# STM32_MPU_IOs.net
KiCad netlist of a schematic drawn in Altium Designer
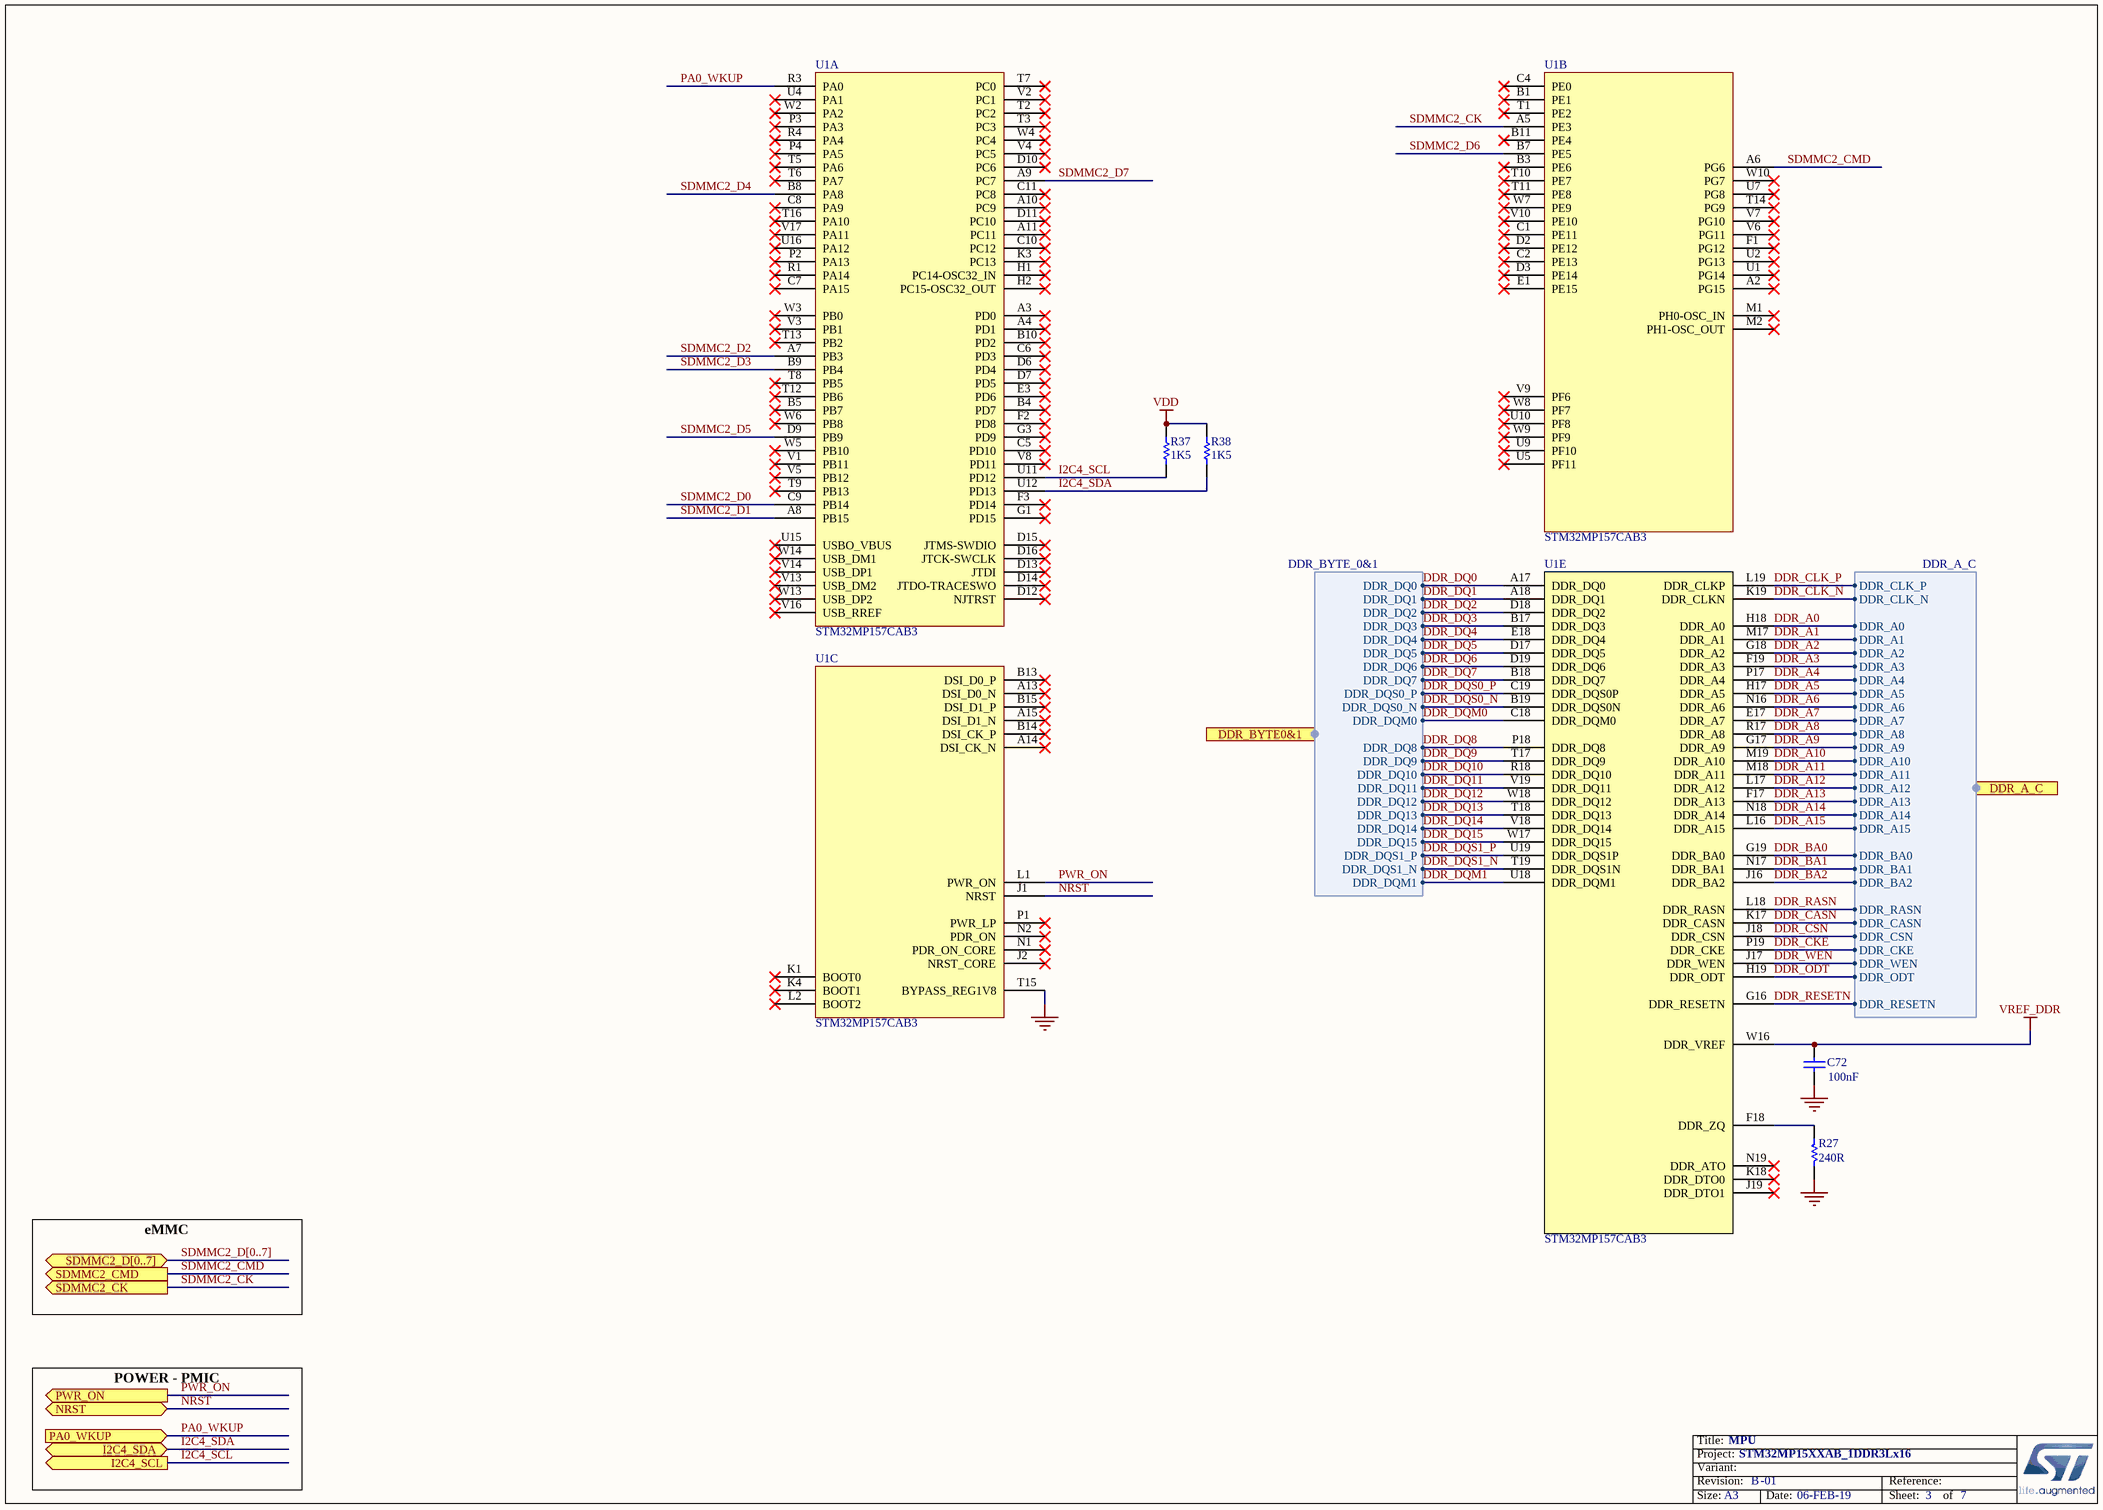
[diagram p0: STM32_MPU_IOs.SchDoc]

(export (version "E")
  (design (tool "Eeschema 10.0.6"))
  (components
    (comp (ref "C72")
      (value "100nF")
      (footprint "C0402")
      (description "Capacitor, MLCC, 100nF, 16V, X7R, 10%, 0402, T=0.5mm")
      (fields
        (field (name "INTERNAL_PART_NUMBER") "MCD-00006")
        (field (name "MANUFACTURER_PART_NUMBER") "CC0402KRX7R7BB104")
        (field (name "PROVIDED_BY") "SUBCO")
      )
      (libsource (lib "MCD_PARTS_database") (part "Capacitor"))
    )
    (comp (ref "R27")
      (value "240R")
      (footprint "R0402")
      (description "Resistor,240R,0402,1%,1/16W")
      (fields
        (field (name "INTERNAL_PART_NUMBER") "MCD-00120")
        (field (name "MANUFACTURER_PART_NUMBER") "RC0402FR-07240RL")
        (field (name "PROVIDED_BY") "SUBCO")
      )
      (libsource (lib "MCD_PARTS_database") (part "Resistor"))
    )
    (comp (ref "R37")
      (value "1K5")
      (footprint "R0402")
      (description "Resistor,1K5,0402,1%,1/16W")
      (fields
        (field (name "INTERNAL_PART_NUMBER") "MCD-00068")
        (field (name "MANUFACTURER_PART_NUMBER") "RC0402FR-071K5L")
        (field (name "PROVIDED_BY") "SUBCO")
      )
      (libsource (lib "MCD_PARTS_database") (part "Resistor"))
    )
    (comp (ref "R38")
      (value "1K5")
      (footprint "R0402")
      (description "Resistor,1K5,0402,1%,1/16W")
      (fields
        (field (name "INTERNAL_PART_NUMBER") "MCD-00068")
        (field (name "MANUFACTURER_PART_NUMBER") "RC0402FR-071K5L")
        (field (name "PROVIDED_BY") "SUBCO")
      )
      (libsource (lib "MCD_PARTS_database") (part "Resistor"))
    )
    (comp (ref "U1")
      (value "STM32MP157CAB3")
      (footprint "ICC_LFBGA354_16X16_STM32MP157CAB3_P080")
      (description "MPU LFBGA 16x16x1.271 PITCH 0.8 mm secure boot + crypto")
      (fields
        (field (name "INTERNAL_PART_NUMBER") "MCD-01805")
        (field (name "MANUFACTURER") "STMICROELECTRONICS")
        (field (name "PROVIDED_BY") "SUBCO with ST control")
      )
      (libsource (lib "MCD_PARTS_database") (part "STM32MP157CAB3"))
    )
  )
  (nets
    (net (code "3") (name "/DDR_A0") (class "Default")
      (node (ref "U1") (pin "H18") (pinfunction "DDR_A0_H18") (pintype "passive"))
    )
    (net (code "4") (name "/DDR_A1") (class "Default")
      (node (ref "U1") (pin "M17") (pinfunction "DDR_A1_M17") (pintype "passive"))
    )
    (net (code "5") (name "/DDR_A2") (class "Default")
      (node (ref "U1") (pin "G18") (pinfunction "DDR_A2_G18") (pintype "passive"))
    )
    (net (code "6") (name "/DDR_A3") (class "Default")
      (node (ref "U1") (pin "F19") (pinfunction "DDR_A3_F19") (pintype "passive"))
    )
    (net (code "7") (name "/DDR_A4") (class "Default")
      (node (ref "U1") (pin "P17") (pinfunction "DDR_A4_P17") (pintype "passive"))
    )
    (net (code "8") (name "/DDR_A5") (class "Default")
      (node (ref "U1") (pin "H17") (pinfunction "DDR_A5_H17") (pintype "passive"))
    )
    (net (code "9") (name "/DDR_A6") (class "Default")
      (node (ref "U1") (pin "N16") (pinfunction "DDR_A6_N16") (pintype "passive"))
    )
    (net (code "10") (name "/DDR_A7") (class "Default")
      (node (ref "U1") (pin "E17") (pinfunction "DDR_A7_E17") (pintype "passive"))
    )
    (net (code "11") (name "/DDR_A8") (class "Default")
      (node (ref "U1") (pin "R17") (pinfunction "DDR_A8_R17") (pintype "passive"))
    )
    (net (code "12") (name "/DDR_A9") (class "Default")
      (node (ref "U1") (pin "G17") (pinfunction "DDR_A9_G17") (pintype "passive"))
    )
    (net (code "13") (name "/DDR_A10") (class "Default")
      (node (ref "U1") (pin "M19") (pinfunction "DDR_A10_M19") (pintype "passive"))
    )
    (net (code "14") (name "/DDR_A11") (class "Default")
      (node (ref "U1") (pin "M18") (pinfunction "DDR_A11_M18") (pintype "passive"))
    )
    (net (code "15") (name "/DDR_A12") (class "Default")
      (node (ref "U1") (pin "L17") (pinfunction "DDR_A12_L17") (pintype "passive"))
    )
    (net (code "16") (name "/DDR_A13") (class "Default")
      (node (ref "U1") (pin "F17") (pinfunction "DDR_A13_F17") (pintype "passive"))
    )
    (net (code "17") (name "/DDR_A14") (class "Default")
      (node (ref "U1") (pin "N18") (pinfunction "DDR_A14_N18") (pintype "passive"))
    )
    (net (code "18") (name "/DDR_A15") (class "Default")
      (node (ref "U1") (pin "L16") (pinfunction "DDR_A15_L16") (pintype "passive"))
    )
    (net (code "19") (name "/DDR_BA0") (class "Default")
      (node (ref "U1") (pin "G19") (pinfunction "DDR_BA0_G19") (pintype "passive"))
    )
    (net (code "20") (name "/DDR_BA1") (class "Default")
      (node (ref "U1") (pin "N17") (pinfunction "DDR_BA1_N17") (pintype "passive"))
    )
    (net (code "21") (name "/DDR_BA2") (class "Default")
      (node (ref "U1") (pin "J16") (pinfunction "DDR_BA2_J16") (pintype "passive"))
    )
    (net (code "22") (name "/DDR_CASN") (class "Default")
      (node (ref "U1") (pin "K17") (pinfunction "DDR_CASN_K17") (pintype "passive"))
    )
    (net (code "23") (name "/DDR_CKE") (class "Default")
      (node (ref "U1") (pin "P19") (pinfunction "DDR_CKE_P19") (pintype "passive"))
    )
    (net (code "24") (name "/DDR_CLK_N") (class "Default")
      (node (ref "U1") (pin "K19") (pinfunction "DDR_CLKN_K19") (pintype "passive"))
    )
    (net (code "25") (name "/DDR_CLK_P") (class "Default")
      (node (ref "U1") (pin "L19") (pinfunction "DDR_CLKP_L19") (pintype "passive"))
    )
    (net (code "26") (name "/DDR_CSN") (class "Default")
      (node (ref "U1") (pin "J18") (pinfunction "DDR_CSN_J18") (pintype "passive"))
    )
    (net (code "27") (name "/DDR_DQ0") (class "Default")
      (node (ref "U1") (pin "A17") (pinfunction "DDR_DQ0_A17") (pintype "passive"))
    )
    (net (code "28") (name "/DDR_DQ1") (class "Default")
      (node (ref "U1") (pin "A18") (pinfunction "DDR_DQ1_A18") (pintype "passive"))
    )
    (net (code "29") (name "/DDR_DQ2") (class "Default")
      (node (ref "U1") (pin "D18") (pinfunction "DDR_DQ2_D18") (pintype "passive"))
    )
    (net (code "30") (name "/DDR_DQ3") (class "Default")
      (node (ref "U1") (pin "B17") (pinfunction "DDR_DQ3_B17") (pintype "passive"))
    )
    (net (code "31") (name "/DDR_DQ4") (class "Default")
      (node (ref "U1") (pin "E18") (pinfunction "DDR_DQ4_E18") (pintype "passive"))
    )
    (net (code "32") (name "/DDR_DQ5") (class "Default")
      (node (ref "U1") (pin "D17") (pinfunction "DDR_DQ5_D17") (pintype "passive"))
    )
    (net (code "33") (name "/DDR_DQ6") (class "Default")
      (node (ref "U1") (pin "D19") (pinfunction "DDR_DQ6_D19") (pintype "passive"))
    )
    (net (code "34") (name "/DDR_DQ7") (class "Default")
      (node (ref "U1") (pin "B18") (pinfunction "DDR_DQ7_B18") (pintype "passive"))
    )
    (net (code "35") (name "/DDR_DQ8") (class "Default")
      (node (ref "U1") (pin "P18") (pinfunction "DDR_DQ8_P18") (pintype "passive"))
    )
    (net (code "36") (name "/DDR_DQ9") (class "Default")
      (node (ref "U1") (pin "T17") (pinfunction "DDR_DQ9_T17") (pintype "passive"))
    )
    (net (code "37") (name "/DDR_DQ10") (class "Default")
      (node (ref "U1") (pin "R18") (pinfunction "DDR_DQ10_R18") (pintype "passive"))
    )
    (net (code "38") (name "/DDR_DQ11") (class "Default")
      (node (ref "U1") (pin "V19") (pinfunction "DDR_DQ11_V19") (pintype "passive"))
    )
    (net (code "39") (name "/DDR_DQ12") (class "Default")
      (node (ref "U1") (pin "W18") (pinfunction "DDR_DQ12_W18") (pintype "passive"))
    )
    (net (code "40") (name "/DDR_DQ13") (class "Default")
      (node (ref "U1") (pin "T18") (pinfunction "DDR_DQ13_T18") (pintype "passive"))
    )
    (net (code "41") (name "/DDR_DQ14") (class "Default")
      (node (ref "U1") (pin "V18") (pinfunction "DDR_DQ14_V18") (pintype "passive"))
    )
    (net (code "42") (name "/DDR_DQ15") (class "Default")
      (node (ref "U1") (pin "W17") (pinfunction "DDR_DQ15_W17") (pintype "passive"))
    )
    (net (code "43") (name "/DDR_DQM0") (class "Default")
      (node (ref "U1") (pin "C18") (pinfunction "DDR_DQM0_C18") (pintype "passive"))
    )
    (net (code "44") (name "/DDR_DQM1") (class "Default")
      (node (ref "U1") (pin "U18") (pinfunction "DDR_DQM1_U18") (pintype "passive"))
    )
    (net (code "45") (name "/DDR_DQS0_N") (class "Default")
      (node (ref "U1") (pin "B19") (pinfunction "DDR_DQS0N_B19") (pintype "passive"))
    )
    (net (code "46") (name "/DDR_DQS0_P") (class "Default")
      (node (ref "U1") (pin "C19") (pinfunction "DDR_DQS0P_C19") (pintype "passive"))
    )
    (net (code "47") (name "/DDR_DQS1_N") (class "Default")
      (node (ref "U1") (pin "T19") (pinfunction "DDR_DQS1N_T19") (pintype "passive"))
    )
    (net (code "48") (name "/DDR_DQS1_P") (class "Default")
      (node (ref "U1") (pin "U19") (pinfunction "DDR_DQS1P_U19") (pintype "passive"))
    )
    (net (code "49") (name "/DDR_ODT") (class "Default")
      (node (ref "U1") (pin "H19") (pinfunction "DDR_ODT_H19") (pintype "passive"))
    )
    (net (code "50") (name "/DDR_RASN") (class "Default")
      (node (ref "U1") (pin "L18") (pinfunction "DDR_RASN_L18") (pintype "passive"))
    )
    (net (code "51") (name "/DDR_RESETN") (class "Default")
      (node (ref "U1") (pin "G16") (pinfunction "DDR_RESETN_G16") (pintype "passive"))
    )
    (net (code "52") (name "/DDR_WEN") (class "Default")
      (node (ref "U1") (pin "J17") (pinfunction "DDR_WEN_J17") (pintype "passive"))
    )
    (net (code "53") (name "/I2C4_SCL") (class "Default")
      (node (ref "R37") (pin "2") (pinfunction "2_2") (pintype "passive"))
      (node (ref "U1") (pin "U11") (pinfunction "PD12_U11") (pintype "passive"))
    )
    (net (code "54") (name "/I2C4_SDA") (class "Default")
      (node (ref "R38") (pin "2") (pinfunction "2_2") (pintype "passive"))
      (node (ref "U1") (pin "U12") (pinfunction "PD13_U12") (pintype "passive"))
    )
    (net (code "55") (name "/NRST") (class "Default")
      (node (ref "U1") (pin "J1") (pinfunction "NRST_J1") (pintype "passive"))
    )
    (net (code "56") (name "/PA0_WKUP") (class "Default")
      (node (ref "U1") (pin "R3") (pinfunction "PA0_R3") (pintype "passive"))
    )
    (net (code "57") (name "/PWR_ON") (class "Default")
      (node (ref "U1") (pin "L1") (pinfunction "PWR_ON_L1") (pintype "passive"))
    )
    (net (code "58") (name "/SDMMC2_CK") (class "Default")
      (node (ref "U1") (pin "A5") (pinfunction "PE3_A5") (pintype "passive"))
    )
    (net (code "59") (name "/SDMMC2_CMD") (class "Default")
      (node (ref "U1") (pin "A6") (pinfunction "PG6_A6") (pintype "passive"))
    )
    (net (code "60") (name "/SDMMC2_D0") (class "Default")
      (node (ref "U1") (pin "C9") (pinfunction "PB14_C9") (pintype "passive"))
    )
    (net (code "61") (name "/SDMMC2_D1") (class "Default")
      (node (ref "U1") (pin "A8") (pinfunction "PB15_A8") (pintype "passive"))
    )
    (net (code "62") (name "/SDMMC2_D2") (class "Default")
      (node (ref "U1") (pin "A7") (pinfunction "PB3_A7") (pintype "passive"))
    )
    (net (code "63") (name "/SDMMC2_D3") (class "Default")
      (node (ref "U1") (pin "B9") (pinfunction "PB4_B9") (pintype "passive"))
    )
    (net (code "64") (name "/SDMMC2_D4") (class "Default")
      (node (ref "U1") (pin "B8") (pinfunction "PA8_B8") (pintype "passive"))
    )
    (net (code "65") (name "/SDMMC2_D5") (class "Default")
      (node (ref "U1") (pin "D9") (pinfunction "PB9_D9") (pintype "passive"))
    )
    (net (code "66") (name "/SDMMC2_D6") (class "Default")
      (node (ref "U1") (pin "B7") (pinfunction "PE5_B7") (pintype "passive"))
    )
    (net (code "67") (name "/SDMMC2_D7") (class "Default")
      (node (ref "U1") (pin "A9") (pinfunction "PC7_A9") (pintype "passive"))
    )
    (net (code "71") (name "GND") (class "Default")
      (node (ref "C72") (pin "1") (pinfunction "1_1") (pintype "passive"))
      (node (ref "R27") (pin "2") (pinfunction "2_2") (pintype "passive"))
      (node (ref "U1") (pin "T15") (pinfunction "BYPASS_REG1V8_T15") (pintype "passive"))
    )
    (net (code "72") (name "Net-(U1E-DDR_ZQ)") (class "Default")
      (node (ref "R27") (pin "1") (pinfunction "1_1") (pintype "passive"))
      (node (ref "U1") (pin "F18") (pinfunction "DDR_ZQ_F18") (pintype "passive"))
    )
    (net (code "73") (name "VDD") (class "Default")
      (node (ref "R37") (pin "1") (pinfunction "1_1") (pintype "passive"))
      (node (ref "R38") (pin "1") (pinfunction "1_1") (pintype "passive"))
    )
    (net (code "74") (name "VREF_DDR") (class "Default")
      (node (ref "C72") (pin "2") (pinfunction "2_2") (pintype "passive"))
      (node (ref "U1") (pin "W16") (pinfunction "DDR_VREF_W16") (pintype "passive"))
    )
    (net (code "75") (name "unconnected-(U1A-JTCK-SWCLK-PadD16)") (class "Default")
      (node (ref "U1") (pin "D16") (pinfunction "JTCK-SWCLK_D16") (pintype "passive+no_connect"))
    )
    (net (code "76") (name "unconnected-(U1A-JTDI-PadD13)") (class "Default")
      (node (ref "U1") (pin "D13") (pinfunction "JTDI_D13") (pintype "passive+no_connect"))
    )
    (net (code "77") (name "unconnected-(U1A-JTDO-TRACESWO-PadD14)") (class "Default")
      (node (ref "U1") (pin "D14") (pinfunction "JTDO-TRACESWO_D14") (pintype "passive+no_connect"))
    )
    (net (code "78") (name "unconnected-(U1A-JTMS-SWDIO-PadD15)") (class "Default")
      (node (ref "U1") (pin "D15") (pinfunction "JTMS-SWDIO_D15") (pintype "passive+no_connect"))
    )
    (net (code "79") (name "unconnected-(U1A-NJTRST-PadD12)") (class "Default")
      (node (ref "U1") (pin "D12") (pinfunction "NJTRST_D12") (pintype "passive+no_connect"))
    )
    (net (code "80") (name "unconnected-(U1A-PA1-PadU4)") (class "Default")
      (node (ref "U1") (pin "U4") (pinfunction "PA1_U4") (pintype "passive+no_connect"))
    )
    (net (code "81") (name "unconnected-(U1A-PA2-PadW2)") (class "Default")
      (node (ref "U1") (pin "W2") (pinfunction "PA2_W2") (pintype "passive+no_connect"))
    )
    (net (code "82") (name "unconnected-(U1A-PA3-PadP3)") (class "Default")
      (node (ref "U1") (pin "P3") (pinfunction "PA3_P3") (pintype "passive+no_connect"))
    )
    (net (code "83") (name "unconnected-(U1A-PA4-PadR4)") (class "Default")
      (node (ref "U1") (pin "R4") (pinfunction "PA4_R4") (pintype "passive+no_connect"))
    )
    (net (code "84") (name "unconnected-(U1A-PA5-PadP4)") (class "Default")
      (node (ref "U1") (pin "P4") (pinfunction "PA5_P4") (pintype "passive+no_connect"))
    )
    (net (code "85") (name "unconnected-(U1A-PA6-PadT5)") (class "Default")
      (node (ref "U1") (pin "T5") (pinfunction "PA6_T5") (pintype "passive+no_connect"))
    )
    (net (code "86") (name "unconnected-(U1A-PA7-PadT6)") (class "Default")
      (node (ref "U1") (pin "T6") (pinfunction "PA7_T6") (pintype "passive+no_connect"))
    )
    (net (code "87") (name "unconnected-(U1A-PA9-PadC8)") (class "Default")
      (node (ref "U1") (pin "C8") (pinfunction "PA9_C8") (pintype "passive+no_connect"))
    )
    (net (code "88") (name "unconnected-(U1A-PA10-PadT16)") (class "Default")
      (node (ref "U1") (pin "T16") (pinfunction "PA10_T16") (pintype "passive+no_connect"))
    )
    (net (code "89") (name "unconnected-(U1A-PA11-PadV17)") (class "Default")
      (node (ref "U1") (pin "V17") (pinfunction "PA11_V17") (pintype "passive+no_connect"))
    )
    (net (code "90") (name "unconnected-(U1A-PA12-PadU16)") (class "Default")
      (node (ref "U1") (pin "U16") (pinfunction "PA12_U16") (pintype "passive+no_connect"))
    )
    (net (code "91") (name "unconnected-(U1A-PA13-PadP2)") (class "Default")
      (node (ref "U1") (pin "P2") (pinfunction "PA13_P2") (pintype "passive+no_connect"))
    )
    (net (code "92") (name "unconnected-(U1A-PA14-PadR1)") (class "Default")
      (node (ref "U1") (pin "R1") (pinfunction "PA14_R1") (pintype "passive+no_connect"))
    )
    (net (code "93") (name "unconnected-(U1A-PA15-PadC7)") (class "Default")
      (node (ref "U1") (pin "C7") (pinfunction "PA15_C7") (pintype "passive+no_connect"))
    )
    (net (code "94") (name "unconnected-(U1A-PB0-PadW3)") (class "Default")
      (node (ref "U1") (pin "W3") (pinfunction "PB0_W3") (pintype "passive+no_connect"))
    )
    (net (code "95") (name "unconnected-(U1A-PB1-PadV3)") (class "Default")
      (node (ref "U1") (pin "V3") (pinfunction "PB1_V3") (pintype "passive+no_connect"))
    )
    (net (code "96") (name "unconnected-(U1A-PB2-PadT13)") (class "Default")
      (node (ref "U1") (pin "T13") (pinfunction "PB2_T13") (pintype "passive+no_connect"))
    )
    (net (code "97") (name "unconnected-(U1A-PB5-PadT8)") (class "Default")
      (node (ref "U1") (pin "T8") (pinfunction "PB5_T8") (pintype "passive+no_connect"))
    )
    (net (code "98") (name "unconnected-(U1A-PB6-PadT12)") (class "Default")
      (node (ref "U1") (pin "T12") (pinfunction "PB6_T12") (pintype "passive+no_connect"))
    )
    (net (code "99") (name "unconnected-(U1A-PB7-PadB5)") (class "Default")
      (node (ref "U1") (pin "B5") (pinfunction "PB7_B5") (pintype "passive+no_connect"))
    )
    (net (code "100") (name "unconnected-(U1A-PB8-PadW6)") (class "Default")
      (node (ref "U1") (pin "W6") (pinfunction "PB8_W6") (pintype "passive+no_connect"))
    )
    (net (code "101") (name "unconnected-(U1A-PB10-PadW5)") (class "Default")
      (node (ref "U1") (pin "W5") (pinfunction "PB10_W5") (pintype "passive+no_connect"))
    )
    (net (code "102") (name "unconnected-(U1A-PB11-PadV1)") (class "Default")
      (node (ref "U1") (pin "V1") (pinfunction "PB11_V1") (pintype "passive+no_connect"))
    )
    (net (code "103") (name "unconnected-(U1A-PB12-PadV5)") (class "Default")
      (node (ref "U1") (pin "V5") (pinfunction "PB12_V5") (pintype "passive+no_connect"))
    )
    (net (code "104") (name "unconnected-(U1A-PB13-PadT9)") (class "Default")
      (node (ref "U1") (pin "T9") (pinfunction "PB13_T9") (pintype "passive+no_connect"))
    )
    (net (code "105") (name "unconnected-(U1A-PC0-PadT7)") (class "Default")
      (node (ref "U1") (pin "T7") (pinfunction "PC0_T7") (pintype "passive+no_connect"))
    )
    (net (code "106") (name "unconnected-(U1A-PC1-PadV2)") (class "Default")
      (node (ref "U1") (pin "V2") (pinfunction "PC1_V2") (pintype "passive+no_connect"))
    )
    (net (code "107") (name "unconnected-(U1A-PC2-PadT2)") (class "Default")
      (node (ref "U1") (pin "T2") (pinfunction "PC2_T2") (pintype "passive+no_connect"))
    )
    (net (code "108") (name "unconnected-(U1A-PC3-PadT3)") (class "Default")
      (node (ref "U1") (pin "T3") (pinfunction "PC3_T3") (pintype "passive+no_connect"))
    )
    (net (code "109") (name "unconnected-(U1A-PC4-PadW4)") (class "Default")
      (node (ref "U1") (pin "W4") (pinfunction "PC4_W4") (pintype "passive+no_connect"))
    )
    (net (code "110") (name "unconnected-(U1A-PC5-PadV4)") (class "Default")
      (node (ref "U1") (pin "V4") (pinfunction "PC5_V4") (pintype "passive+no_connect"))
    )
    (net (code "111") (name "unconnected-(U1A-PC6-PadD10)") (class "Default")
      (node (ref "U1") (pin "D10") (pinfunction "PC6_D10") (pintype "passive+no_connect"))
    )
    (net (code "112") (name "unconnected-(U1A-PC8-PadC11)") (class "Default")
      (node (ref "U1") (pin "C11") (pinfunction "PC8_C11") (pintype "passive+no_connect"))
    )
    (net (code "113") (name "unconnected-(U1A-PC9-PadA10)") (class "Default")
      (node (ref "U1") (pin "A10") (pinfunction "PC9_A10") (pintype "passive+no_connect"))
    )
    (net (code "114") (name "unconnected-(U1A-PC10-PadD11)") (class "Default")
      (node (ref "U1") (pin "D11") (pinfunction "PC10_D11") (pintype "passive+no_connect"))
    )
    (net (code "115") (name "unconnected-(U1A-PC11-PadA11)") (class "Default")
      (node (ref "U1") (pin "A11") (pinfunction "PC11_A11") (pintype "passive+no_connect"))
    )
    (net (code "116") (name "unconnected-(U1A-PC12-PadC10)") (class "Default")
      (node (ref "U1") (pin "C10") (pinfunction "PC12_C10") (pintype "passive+no_connect"))
    )
    (net (code "117") (name "unconnected-(U1A-PC13-PadK3)") (class "Default")
      (node (ref "U1") (pin "K3") (pinfunction "PC13_K3") (pintype "passive+no_connect"))
    )
    (net (code "118") (name "unconnected-(U1A-PC14-OSC32_IN-PadH1)") (class "Default")
      (node (ref "U1") (pin "H1") (pinfunction "PC14-OSC32_IN_H1") (pintype "passive+no_connect"))
    )
    (net (code "119") (name "unconnected-(U1A-PC15-OSC32_OUT-PadH2)") (class "Default")
      (node (ref "U1") (pin "H2") (pinfunction "PC15-OSC32_OUT_H2") (pintype "passive+no_connect"))
    )
    (net (code "120") (name "unconnected-(U1A-PD0-PadA3)") (class "Default")
      (node (ref "U1") (pin "A3") (pinfunction "PD0_A3") (pintype "passive+no_connect"))
    )
    (net (code "121") (name "unconnected-(U1A-PD1-PadA4)") (class "Default")
      (node (ref "U1") (pin "A4") (pinfunction "PD1_A4") (pintype "passive+no_connect"))
    )
    (net (code "122") (name "unconnected-(U1A-PD2-PadB10)") (class "Default")
      (node (ref "U1") (pin "B10") (pinfunction "PD2_B10") (pintype "passive+no_connect"))
    )
    (net (code "123") (name "unconnected-(U1A-PD3-PadC6)") (class "Default")
      (node (ref "U1") (pin "C6") (pinfunction "PD3_C6") (pintype "passive+no_connect"))
    )
    (net (code "124") (name "unconnected-(U1A-PD4-PadD6)") (class "Default")
      (node (ref "U1") (pin "D6") (pinfunction "PD4_D6") (pintype "passive+no_connect"))
    )
    (net (code "125") (name "unconnected-(U1A-PD5-PadD7)") (class "Default")
      (node (ref "U1") (pin "D7") (pinfunction "PD5_D7") (pintype "passive+no_connect"))
    )
    (net (code "126") (name "unconnected-(U1A-PD6-PadE3)") (class "Default")
      (node (ref "U1") (pin "E3") (pinfunction "PD6_E3") (pintype "passive+no_connect"))
    )
    (net (code "127") (name "unconnected-(U1A-PD7-PadB4)") (class "Default")
      (node (ref "U1") (pin "B4") (pinfunction "PD7_B4") (pintype "passive+no_connect"))
    )
    (net (code "128") (name "unconnected-(U1A-PD8-PadF2)") (class "Default")
      (node (ref "U1") (pin "F2") (pinfunction "PD8_F2") (pintype "passive+no_connect"))
    )
    (net (code "129") (name "unconnected-(U1A-PD9-PadG3)") (class "Default")
      (node (ref "U1") (pin "G3") (pinfunction "PD9_G3") (pintype "passive+no_connect"))
    )
    (net (code "130") (name "unconnected-(U1A-PD10-PadC5)") (class "Default")
      (node (ref "U1") (pin "C5") (pinfunction "PD10_C5") (pintype "passive+no_connect"))
    )
    (net (code "131") (name "unconnected-(U1A-PD11-PadV8)") (class "Default")
      (node (ref "U1") (pin "V8") (pinfunction "PD11_V8") (pintype "passive+no_connect"))
    )
    (net (code "132") (name "unconnected-(U1A-PD14-PadF3)") (class "Default")
      (node (ref "U1") (pin "F3") (pinfunction "PD14_F3") (pintype "passive+no_connect"))
    )
    (net (code "133") (name "unconnected-(U1A-PD15-PadG1)") (class "Default")
      (node (ref "U1") (pin "G1") (pinfunction "PD15_G1") (pintype "passive+no_connect"))
    )
    (net (code "134") (name "unconnected-(U1A-USBO_VBUS-PadU15)") (class "Default")
      (node (ref "U1") (pin "U15") (pinfunction "USBO_VBUS_U15") (pintype "passive+no_connect"))
    )
    (net (code "135") (name "unconnected-(U1A-USB_DM1-PadW14)") (class "Default")
      (node (ref "U1") (pin "W14") (pinfunction "USB_DM1_W14") (pintype "passive+no_connect"))
    )
    (net (code "136") (name "unconnected-(U1A-USB_DM2-PadV13)") (class "Default")
      (node (ref "U1") (pin "V13") (pinfunction "USB_DM2_V13") (pintype "passive+no_connect"))
    )
    (net (code "137") (name "unconnected-(U1A-USB_DP1-PadV14)") (class "Default")
      (node (ref "U1") (pin "V14") (pinfunction "USB_DP1_V14") (pintype "passive+no_connect"))
    )
    (net (code "138") (name "unconnected-(U1A-USB_DP2-PadW13)") (class "Default")
      (node (ref "U1") (pin "W13") (pinfunction "USB_DP2_W13") (pintype "passive+no_connect"))
    )
    (net (code "139") (name "unconnected-(U1A-USB_RREF-PadV16)") (class "Default")
      (node (ref "U1") (pin "V16") (pinfunction "USB_RREF_V16") (pintype "passive+no_connect"))
    )
    (net (code "140") (name "unconnected-(U1B-PE0-PadC4)") (class "Default")
      (node (ref "U1") (pin "C4") (pinfunction "PE0_C4") (pintype "passive+no_connect"))
    )
    (net (code "141") (name "unconnected-(U1B-PE1-PadB1)") (class "Default")
      (node (ref "U1") (pin "B1") (pinfunction "PE1_B1") (pintype "passive+no_connect"))
    )
    (net (code "142") (name "unconnected-(U1B-PE2-PadT1)") (class "Default")
      (node (ref "U1") (pin "T1") (pinfunction "PE2_T1") (pintype "passive+no_connect"))
    )
    (net (code "143") (name "unconnected-(U1B-PE4-PadB11)") (class "Default")
      (node (ref "U1") (pin "B11") (pinfunction "PE4_B11") (pintype "passive+no_connect"))
    )
    (net (code "144") (name "unconnected-(U1B-PE6-PadB3)") (class "Default")
      (node (ref "U1") (pin "B3") (pinfunction "PE6_B3") (pintype "passive+no_connect"))
    )
    (net (code "145") (name "unconnected-(U1B-PE7-PadT10)") (class "Default")
      (node (ref "U1") (pin "T10") (pinfunction "PE7_T10") (pintype "passive+no_connect"))
    )
    (net (code "146") (name "unconnected-(U1B-PE8-PadT11)") (class "Default")
      (node (ref "U1") (pin "T11") (pinfunction "PE8_T11") (pintype "passive+no_connect"))
    )
    (net (code "147") (name "unconnected-(U1B-PE9-PadW7)") (class "Default")
      (node (ref "U1") (pin "W7") (pinfunction "PE9_W7") (pintype "passive+no_connect"))
    )
    (net (code "148") (name "unconnected-(U1B-PE10-PadV10)") (class "Default")
      (node (ref "U1") (pin "V10") (pinfunction "PE10_V10") (pintype "passive+no_connect"))
    )
    (net (code "149") (name "unconnected-(U1B-PE11-PadC1)") (class "Default")
      (node (ref "U1") (pin "C1") (pinfunction "PE11_C1") (pintype "passive+no_connect"))
    )
    (net (code "150") (name "unconnected-(U1B-PE12-PadD2)") (class "Default")
      (node (ref "U1") (pin "D2") (pinfunction "PE12_D2") (pintype "passive+no_connect"))
    )
    (net (code "151") (name "unconnected-(U1B-PE13-PadC2)") (class "Default")
      (node (ref "U1") (pin "C2") (pinfunction "PE13_C2") (pintype "passive+no_connect"))
    )
    (net (code "152") (name "unconnected-(U1B-PE14-PadD3)") (class "Default")
      (node (ref "U1") (pin "D3") (pinfunction "PE14_D3") (pintype "passive+no_connect"))
    )
    (net (code "153") (name "unconnected-(U1B-PE15-PadE1)") (class "Default")
      (node (ref "U1") (pin "E1") (pinfunction "PE15_E1") (pintype "passive+no_connect"))
    )
    (net (code "154") (name "unconnected-(U1B-PF6-PadV9)") (class "Default")
      (node (ref "U1") (pin "V9") (pinfunction "PF6_V9") (pintype "passive+no_connect"))
    )
    (net (code "155") (name "unconnected-(U1B-PF7-PadW8)") (class "Default")
      (node (ref "U1") (pin "W8") (pinfunction "PF7_W8") (pintype "passive+no_connect"))
    )
    (net (code "156") (name "unconnected-(U1B-PF8-PadU10)") (class "Default")
      (node (ref "U1") (pin "U10") (pinfunction "PF8_U10") (pintype "passive+no_connect"))
    )
    (net (code "157") (name "unconnected-(U1B-PF9-PadW9)") (class "Default")
      (node (ref "U1") (pin "W9") (pinfunction "PF9_W9") (pintype "passive+no_connect"))
    )
    (net (code "158") (name "unconnected-(U1B-PF10-PadU9)") (class "Default")
      (node (ref "U1") (pin "U9") (pinfunction "PF10_U9") (pintype "passive+no_connect"))
    )
    (net (code "159") (name "unconnected-(U1B-PF11-PadU5)") (class "Default")
      (node (ref "U1") (pin "U5") (pinfunction "PF11_U5") (pintype "passive+no_connect"))
    )
    (net (code "160") (name "unconnected-(U1B-PG7-PadW10)") (class "Default")
      (node (ref "U1") (pin "W10") (pinfunction "PG7_W10") (pintype "passive+no_connect"))
    )
    (net (code "161") (name "unconnected-(U1B-PG8-PadU7)") (class "Default")
      (node (ref "U1") (pin "U7") (pinfunction "PG8_U7") (pintype "passive+no_connect"))
    )
    (net (code "162") (name "unconnected-(U1B-PG9-PadT14)") (class "Default")
      (node (ref "U1") (pin "T14") (pinfunction "PG9_T14") (pintype "passive+no_connect"))
    )
    (net (code "163") (name "unconnected-(U1B-PG10-PadV7)") (class "Default")
      (node (ref "U1") (pin "V7") (pinfunction "PG10_V7") (pintype "passive+no_connect"))
    )
    (net (code "164") (name "unconnected-(U1B-PG11-PadV6)") (class "Default")
      (node (ref "U1") (pin "V6") (pinfunction "PG11_V6") (pintype "passive+no_connect"))
    )
    (net (code "165") (name "unconnected-(U1B-PG12-PadF1)") (class "Default")
      (node (ref "U1") (pin "F1") (pinfunction "PG12_F1") (pintype "passive+no_connect"))
    )
    (net (code "166") (name "unconnected-(U1B-PG13-PadU2)") (class "Default")
      (node (ref "U1") (pin "U2") (pinfunction "PG13_U2") (pintype "passive+no_connect"))
    )
    (net (code "167") (name "unconnected-(U1B-PG14-PadU1)") (class "Default")
      (node (ref "U1") (pin "U1") (pinfunction "PG14_U1") (pintype "passive+no_connect"))
    )
    (net (code "168") (name "unconnected-(U1B-PG15-PadA2)") (class "Default")
      (node (ref "U1") (pin "A2") (pinfunction "PG15_A2") (pintype "passive+no_connect"))
    )
    (net (code "169") (name "unconnected-(U1B-PH0-OSC_IN-PadM1)") (class "Default")
      (node (ref "U1") (pin "M1") (pinfunction "PH0-OSC_IN_M1") (pintype "passive+no_connect"))
    )
    (net (code "170") (name "unconnected-(U1B-PH1-OSC_OUT-PadM2)") (class "Default")
      (node (ref "U1") (pin "M2") (pinfunction "PH1-OSC_OUT_M2") (pintype "passive+no_connect"))
    )
    (net (code "171") (name "unconnected-(U1C-BOOT0-PadK1)") (class "Default")
      (node (ref "U1") (pin "K1") (pinfunction "BOOT0_K1") (pintype "passive+no_connect"))
    )
    (net (code "172") (name "unconnected-(U1C-BOOT1-PadK4)") (class "Default")
      (node (ref "U1") (pin "K4") (pinfunction "BOOT1_K4") (pintype "passive+no_connect"))
    )
    (net (code "173") (name "unconnected-(U1C-BOOT2-PadL2)") (class "Default")
      (node (ref "U1") (pin "L2") (pinfunction "BOOT2_L2") (pintype "passive+no_connect"))
    )
    (net (code "174") (name "unconnected-(U1C-DSI_CK_N-PadA14)") (class "Default")
      (node (ref "U1") (pin "A14") (pinfunction "DSI_CK_N_A14") (pintype "passive+no_connect"))
    )
    (net (code "175") (name "unconnected-(U1C-DSI_CK_P-PadB14)") (class "Default")
      (node (ref "U1") (pin "B14") (pinfunction "DSI_CK_P_B14") (pintype "passive+no_connect"))
    )
    (net (code "176") (name "unconnected-(U1C-DSI_D0_N-PadA13)") (class "Default")
      (node (ref "U1") (pin "A13") (pinfunction "DSI_D0_N_A13") (pintype "passive+no_connect"))
    )
    (net (code "177") (name "unconnected-(U1C-DSI_D0_P-PadB13)") (class "Default")
      (node (ref "U1") (pin "B13") (pinfunction "DSI_D0_P_B13") (pintype "passive+no_connect"))
    )
    (net (code "178") (name "unconnected-(U1C-DSI_D1_N-PadA15)") (class "Default")
      (node (ref "U1") (pin "A15") (pinfunction "DSI_D1_N_A15") (pintype "passive+no_connect"))
    )
    (net (code "179") (name "unconnected-(U1C-DSI_D1_P-PadB15)") (class "Default")
      (node (ref "U1") (pin "B15") (pinfunction "DSI_D1_P_B15") (pintype "passive+no_connect"))
    )
    (net (code "180") (name "unconnected-(U1C-NRST_CORE-PadJ2)") (class "Default")
      (node (ref "U1") (pin "J2") (pinfunction "NRST_CORE_J2") (pintype "passive+no_connect"))
    )
    (net (code "181") (name "unconnected-(U1C-PDR_ON-PadN2)") (class "Default")
      (node (ref "U1") (pin "N2") (pinfunction "PDR_ON_N2") (pintype "passive+no_connect"))
    )
    (net (code "182") (name "unconnected-(U1C-PDR_ON_CORE-PadN1)") (class "Default")
      (node (ref "U1") (pin "N1") (pinfunction "PDR_ON_CORE_N1") (pintype "passive+no_connect"))
    )
    (net (code "183") (name "unconnected-(U1C-PWR_LP-PadP1)") (class "Default")
      (node (ref "U1") (pin "P1") (pinfunction "PWR_LP_P1") (pintype "passive+no_connect"))
    )
    (net (code "184") (name "unconnected-(U1E-DDR_ATO-PadN19)") (class "Default")
      (node (ref "U1") (pin "N19") (pinfunction "DDR_ATO_N19") (pintype "passive+no_connect"))
    )
    (net (code "185") (name "unconnected-(U1E-DDR_DTO0-PadK18)") (class "Default")
      (node (ref "U1") (pin "K18") (pinfunction "DDR_DTO0_K18") (pintype "passive+no_connect"))
    )
    (net (code "186") (name "unconnected-(U1E-DDR_DTO1-PadJ19)") (class "Default")
      (node (ref "U1") (pin "J19") (pinfunction "DDR_DTO1_J19") (pintype "passive+no_connect"))
    )
  )
)
